# autorewers_Atmega_6.net
KiCad netlist of a schematic drawn in EAGLE
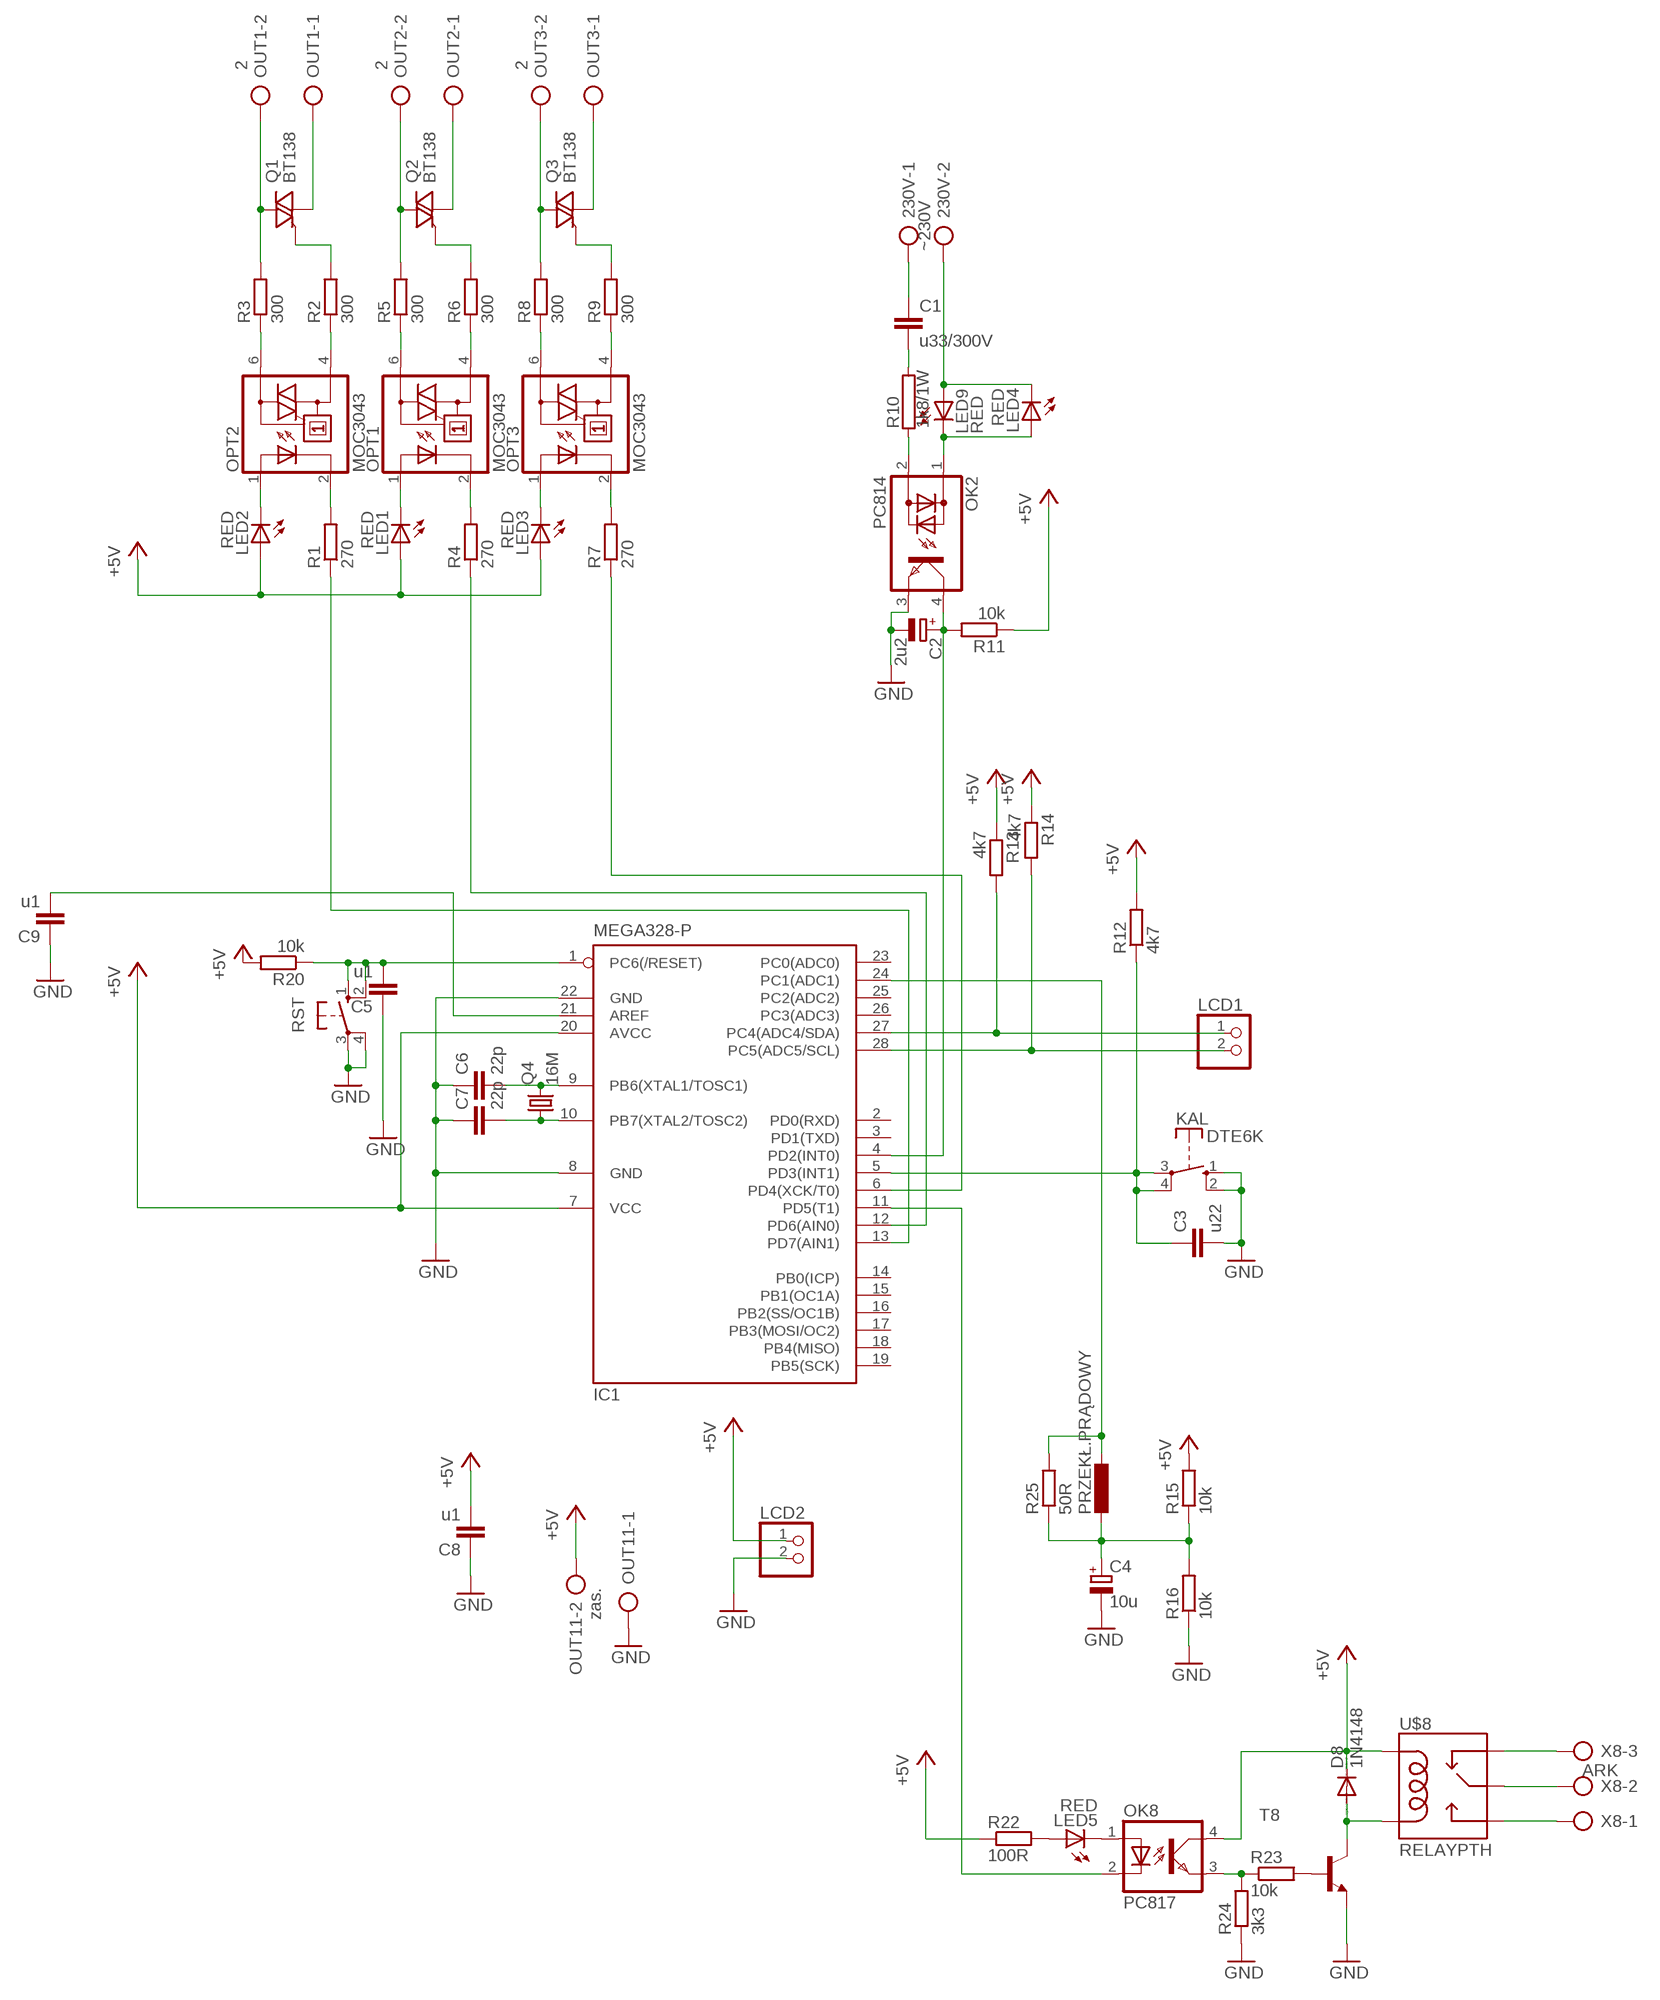
[diagram p0: schematic, sheet 1]

(export (version "E")
  (design (tool "Eeschema 10.0.6"))
  (components
    (comp (ref "230V")
      (value "~230V")
      (footprint "eagle-import:AK500_2")
      (libsource (lib "eagle-import") (part "AK500/2"))
    )
    (comp (ref "C1")
      (value "u33/300V")
      (footprint "eagle-import:C225-087X268")
      (libsource (lib "eagle-import") (part "C-EU225-087X268"))
    )
    (comp (ref "C2")
      (value "2u2")
      (footprint "eagle-import:B45181A")
      (libsource (lib "eagle-import") (part "CPOL-EUB45181A"))
    )
    (comp (ref "C3")
      (value "u22")
      (footprint "eagle-import:C050-025X075")
      (libsource (lib "eagle-import") (part "C-EU050-025X075"))
    )
    (comp (ref "C4")
      (value "10u")
      (footprint "eagle-import:B45181A")
      (libsource (lib "eagle-import") (part "CPOL-EUB45181A"))
    )
    (comp (ref "C5")
      (value "u1")
      (footprint "eagle-import:C050-025X075")
      (libsource (lib "eagle-import") (part "C-EU050-025X075"))
    )
    (comp (ref "C6")
      (value "22p")
      (footprint "eagle-import:C050-025X075")
      (libsource (lib "eagle-import") (part "C-EU050-025X075"))
    )
    (comp (ref "C7")
      (value "22p")
      (footprint "eagle-import:C050-025X075")
      (libsource (lib "eagle-import") (part "C-EU050-025X075"))
    )
    (comp (ref "C8")
      (value "u1")
      (footprint "eagle-import:C050-025X075")
      (libsource (lib "eagle-import") (part "C-EU050-025X075"))
    )
    (comp (ref "C9")
      (value "u1")
      (footprint "eagle-import:C050-025X075")
      (libsource (lib "eagle-import") (part "C-EU050-025X075"))
    )
    (comp (ref "D8")
      (value "1N4148")
      (footprint "eagle-import:DO35-10")
      (libsource (lib "eagle-import") (part "1N4148DO35-10"))
    )
    (comp (ref "IC1")
      (value "MEGA328-P")
      (footprint "eagle-import:DIL28-3")
      (libsource (lib "eagle-import") (part "MEGA8-P"))
    )
    (comp (ref "KAL")
      (value "DTE6K")
      (footprint "eagle-import:DTE6K")
      (libsource (lib "eagle-import") (part "DTE6K"))
    )
    (comp (ref "LCD1")
      (value "PINHD-1X2")
      (footprint "eagle-import:1X02")
      (libsource (lib "eagle-import") (part "PINHD-1X2"))
    )
    (comp (ref "LCD2")
      (value "PINHD-1X2")
      (footprint "eagle-import:1X02")
      (libsource (lib "eagle-import") (part "PINHD-1X2"))
    )
    (comp (ref "LED1")
      (value "RED")
      (footprint "eagle-import:LED3MM")
      (libsource (lib "eagle-import") (part "LED3MM"))
    )
    (comp (ref "LED2")
      (value "RED")
      (footprint "eagle-import:LED3MM")
      (libsource (lib "eagle-import") (part "LED3MM"))
    )
    (comp (ref "LED3")
      (value "RED")
      (footprint "eagle-import:LED3MM")
      (libsource (lib "eagle-import") (part "LED3MM"))
    )
    (comp (ref "LED4")
      (value "RED")
      (footprint "eagle-import:LED3MM")
      (libsource (lib "eagle-import") (part "LED3MM"))
    )
    (comp (ref "LED5")
      (value "RED")
      (footprint "eagle-import:LED3MM")
      (libsource (lib "eagle-import") (part "LED3MM"))
    )
    (comp (ref "LED9")
      (value "RED")
      (footprint "eagle-import:LED3MM")
      (libsource (lib "eagle-import") (part "LED3MM"))
    )
    (comp (ref "OK2")
      (value "PC814")
      (footprint "eagle-import:DIL04")
      (libsource (lib "eagle-import") (part "PC814"))
    )
    (comp (ref "OK8")
      (value "PC817")
      (footprint "eagle-import:DIL04")
      (fields (field (name "MPN") "PC817X4J000F"))
      (libsource (lib "eagle-import") (part "PC817"))
    )
    (comp (ref "OPT1")
      (value "MOC3043")
      (footprint "eagle-import:DIL06")
      (fields
        (field (name "MF") "VISHAY/TELEFUNKEN")
        (field (name "MPN") "IL410")
        (field (name "MF_1") "FAIRCHILD SEMICONDUCTOR")
        (field (name "MPN_1") "MOC3041")
      )
      (libsource (lib "eagle-import") (part "IL410"))
    )
    (comp (ref "OPT2")
      (value "MOC3043")
      (footprint "eagle-import:DIL06")
      (fields
        (field (name "MF") "VISHAY/TELEFUNKEN")
        (field (name "MPN") "IL410")
        (field (name "MF_1") "FAIRCHILD SEMICONDUCTOR")
        (field (name "MPN_1") "MOC3041")
      )
      (libsource (lib "eagle-import") (part "IL410"))
    )
    (comp (ref "OPT3")
      (value "MOC3043")
      (footprint "eagle-import:DIL06")
      (fields
        (field (name "MF") "VISHAY/TELEFUNKEN")
        (field (name "MPN") "IL410")
        (field (name "MF_1") "FAIRCHILD SEMICONDUCTOR")
        (field (name "MPN_1") "MOC3041")
      )
      (libsource (lib "eagle-import") (part "IL410"))
    )
    (comp (ref "OUT1")
      (value "2")
      (footprint "eagle-import:AK500_2")
      (libsource (lib "eagle-import") (part "AK500/2"))
    )
    (comp (ref "OUT2")
      (value "2")
      (footprint "eagle-import:AK500_2")
      (libsource (lib "eagle-import") (part "AK500/2"))
    )
    (comp (ref "OUT3")
      (value "2")
      (footprint "eagle-import:AK500_2")
      (libsource (lib "eagle-import") (part "AK500/2"))
    )
    (comp (ref "OUT11")
      (value "zas.")
      (footprint "eagle-import:AK500_2")
      (libsource (lib "eagle-import") (part "AK500/2"))
    )
    (comp (ref "PRZEKŁ.PRĄDOWY")
      (value "L-EU2200-12.7")
      (footprint "eagle-import:2200-12.7")
      (libsource (lib "eagle-import") (part "L-EU2200-12.7"))
    )
    (comp (ref "Q1")
      (value "BT138")
      (footprint "eagle-import:TO220BV")
      (libsource (lib "eagle-import") (part "BT138-V"))
    )
    (comp (ref "Q2")
      (value "BT138")
      (footprint "eagle-import:TO220BV")
      (libsource (lib "eagle-import") (part "BT138-V"))
    )
    (comp (ref "Q3")
      (value "BT138")
      (footprint "eagle-import:TO220BV")
      (libsource (lib "eagle-import") (part "BT138-V"))
    )
    (comp (ref "Q4")
      (value "16M")
      (footprint "eagle-import:HC49_S")
      (libsource (lib "eagle-import") (part "CRYSTALHC49S"))
    )
    (comp (ref "R1")
      (value "270")
      (footprint "eagle-import:0204_7")
      (libsource (lib "eagle-import") (part "R-EU_0204/7"))
    )
    (comp (ref "R2")
      (value "300")
      (footprint "eagle-import:0204_7")
      (libsource (lib "eagle-import") (part "R-EU_0204/7"))
    )
    (comp (ref "R3")
      (value "300")
      (footprint "eagle-import:0204_7")
      (libsource (lib "eagle-import") (part "R-EU_0204/7"))
    )
    (comp (ref "R4")
      (value "270")
      (footprint "eagle-import:0204_5")
      (libsource (lib "eagle-import") (part "R-EU_0204/5"))
    )
    (comp (ref "R5")
      (value "300")
      (footprint "eagle-import:0204_7")
      (libsource (lib "eagle-import") (part "R-EU_0204/7"))
    )
    (comp (ref "R6")
      (value "300")
      (footprint "eagle-import:0204_7")
      (libsource (lib "eagle-import") (part "R-EU_0204/7"))
    )
    (comp (ref "R7")
      (value "270")
      (footprint "eagle-import:0617_22")
      (libsource (lib "eagle-import") (part "R-EU_0617/22"))
    )
    (comp (ref "R8")
      (value "300")
      (footprint "eagle-import:0204_7")
      (libsource (lib "eagle-import") (part "R-EU_0204/7"))
    )
    (comp (ref "R9")
      (value "300")
      (footprint "eagle-import:0204_7")
      (libsource (lib "eagle-import") (part "R-EU_0204/7"))
    )
    (comp (ref "R10")
      (value "1k8/1W")
      (footprint "eagle-import:AC01")
      (libsource (lib "eagle-import") (part "RAC01"))
    )
    (comp (ref "R11")
      (value "10k")
      (footprint "eagle-import:0207_10")
      (libsource (lib "eagle-import") (part "R-EU_0207/10"))
    )
    (comp (ref "R12")
      (value "4k7")
      (footprint "eagle-import:0204_7")
      (libsource (lib "eagle-import") (part "R-EU_0204/7"))
    )
    (comp (ref "R13")
      (value "4k7")
      (footprint "eagle-import:0204_7")
      (libsource (lib "eagle-import") (part "R-EU_0204/7"))
    )
    (comp (ref "R14")
      (value "4k7")
      (footprint "eagle-import:0204_7")
      (libsource (lib "eagle-import") (part "R-EU_0204/7"))
    )
    (comp (ref "R15")
      (value "10k")
      (footprint "eagle-import:0204_7")
      (libsource (lib "eagle-import") (part "R-EU_0204/7"))
    )
    (comp (ref "R16")
      (value "10k")
      (footprint "eagle-import:0204_7")
      (libsource (lib "eagle-import") (part "R-EU_0204/7"))
    )
    (comp (ref "R20")
      (value "10k")
      (footprint "eagle-import:0207_15")
      (libsource (lib "eagle-import") (part "R-EU_0207/15"))
    )
    (comp (ref "R22")
      (value "100R")
      (footprint "eagle-import:0207_10")
      (libsource (lib "eagle-import") (part "resistor_R-EU_0207/10"))
    )
    (comp (ref "R23")
      (value "10k")
      (footprint "eagle-import:0204_5")
      (libsource (lib "eagle-import") (part "resistor_R-EU_0204/5"))
    )
    (comp (ref "R24")
      (value "3k3")
      (footprint "eagle-import:0204_7")
      (libsource (lib "eagle-import") (part "resistor_R-EU_0204/7"))
    )
    (comp (ref "R25")
      (value "50R")
      (footprint "eagle-import:0204_7")
      (libsource (lib "eagle-import") (part "R-EU_0204/7"))
    )
    (comp (ref "RST")
      (value "10-XX")
      (footprint "eagle-import:B3F-10XX")
      (fields (field (name "MPN") "B3F-1000"))
      (libsource (lib "eagle-import") (part "10-XX"))
    )
    (comp (ref "T8")
      (value "BC237-NPN-TO92-CBE")
      (footprint "eagle-import:TO92-CBE")
      (libsource (lib "eagle-import") (part "-NPN-TO92-CBEBC237"))
    )
    (comp (ref "U$8")
      (value "RELAYPTH")
      (footprint "eagle-import:SRD-05VDC-SL-C")
      (libsource (lib "eagle-import") (part "RELAYPTH"))
    )
    (comp (ref "X8")
      (value "ARK")
      (footprint "eagle-import:AK300_3")
      (libsource (lib "eagle-import") (part "AK300/3"))
    )
  )
  (nets
    (net (code "1") (name "+5V") (class "Default")
      (node (ref "C8") (pin "2") (pinfunction "2_2") (pintype "passive"))
      (node (ref "D8") (pin "C") (pinfunction "C_C") (pintype "passive"))
      (node (ref "IC1") (pin "20") (pinfunction "AVCC_20") (pintype "power_in"))
      (node (ref "IC1") (pin "7") (pinfunction "VCC_7") (pintype "power_in"))
      (node (ref "LCD2") (pin "1") (pinfunction "1_1") (pintype "passive"))
      (node (ref "LED1") (pin "A") (pinfunction "A_A") (pintype "passive"))
      (node (ref "LED2") (pin "A") (pinfunction "A_A") (pintype "passive"))
      (node (ref "LED3") (pin "A") (pinfunction "A_A") (pintype "passive"))
      (node (ref "OK8") (pin "4") (pinfunction "COL_4") (pintype "passive"))
      (node (ref "OUT11") (pin "2") (pinfunction "KL_2") (pintype "passive"))
      (node (ref "R11") (pin "1") (pinfunction "1_1") (pintype "passive"))
      (node (ref "R12") (pin "2") (pinfunction "2_2") (pintype "passive"))
      (node (ref "R13") (pin "1") (pinfunction "1_1") (pintype "passive"))
      (node (ref "R14") (pin "1") (pinfunction "1_1") (pintype "passive"))
      (node (ref "R15") (pin "2") (pinfunction "2_2") (pintype "passive"))
      (node (ref "R20") (pin "2") (pinfunction "2_2") (pintype "passive"))
      (node (ref "R22") (pin "1") (pinfunction "1_1") (pintype "passive"))
      (node (ref "U$8") (pin "COIL1") (pinfunction "COIL1_COIL1") (pintype "bidirectional"))
    )
    (net (code "2") (name "GND") (class "Default")
      (node (ref "C2") (pin "-") (pinfunction "-_-") (pintype "passive"))
      (node (ref "C3") (pin "2") (pinfunction "2_2") (pintype "passive"))
      (node (ref "C4") (pin "-") (pinfunction "-_-") (pintype "passive"))
      (node (ref "C5") (pin "1") (pinfunction "1_1") (pintype "passive"))
      (node (ref "C6") (pin "1") (pinfunction "1_1") (pintype "passive"))
      (node (ref "C7") (pin "1") (pinfunction "1_1") (pintype "passive"))
      (node (ref "C8") (pin "1") (pinfunction "1_1") (pintype "passive"))
      (node (ref "C9") (pin "1") (pinfunction "1_1") (pintype "passive"))
      (node (ref "IC1") (pin "22") (pinfunction "GND_22") (pintype "power_in"))
      (node (ref "IC1") (pin "8") (pinfunction "GND_8") (pintype "power_in"))
      (node (ref "KAL") (pin "1") (pinfunction "S_1") (pintype "passive"))
      (node (ref "KAL") (pin "2") (pinfunction "S_2") (pintype "passive"))
      (node (ref "LCD2") (pin "2") (pinfunction "2_2") (pintype "passive"))
      (node (ref "OK2") (pin "3") (pinfunction "E_3") (pintype "passive"))
      (node (ref "OUT11") (pin "1") (pinfunction "KL_1") (pintype "passive"))
      (node (ref "R16") (pin "1") (pinfunction "1_1") (pintype "passive"))
      (node (ref "R24") (pin "1") (pinfunction "1_1") (pintype "passive"))
      (node (ref "RST") (pin "3") (pinfunction "P_3") (pintype "passive"))
      (node (ref "RST") (pin "4") (pinfunction "P1_4") (pintype "passive"))
      (node (ref "T8") (pin "E") (pinfunction "E_E") (pintype "passive"))
    )
    (net (code "3") (name "Net-(230VA-KL)") (class "Default")
      (node (ref "230V") (pin "1") (pinfunction "KL_1") (pintype "passive"))
      (node (ref "C1") (pin "1") (pinfunction "1_1") (pintype "passive"))
    )
    (net (code "4") (name "Net-(230VB-KL)") (class "Default")
      (node (ref "230V") (pin "2") (pinfunction "KL_2") (pintype "passive"))
      (node (ref "LED4") (pin "K") (pinfunction "C_K") (pintype "passive"))
      (node (ref "LED9") (pin "A") (pinfunction "A_A") (pintype "passive"))
    )
    (net (code "5") (name "Net-(C1-Pad2)") (class "Default")
      (node (ref "C1") (pin "2") (pinfunction "2_2") (pintype "passive"))
      (node (ref "R10") (pin "2") (pinfunction "2_2") (pintype "passive"))
    )
    (net (code "6") (name "Net-(C4-Pad+)") (class "Default")
      (node (ref "C4") (pin "+") (pinfunction "+_+") (pintype "passive"))
      (node (ref "PRZEKŁ.PRĄDOWY") (pin "2") (pinfunction "2_2") (pintype "passive"))
      (node (ref "R15") (pin "1") (pinfunction "1_1") (pintype "passive"))
      (node (ref "R16") (pin "2") (pinfunction "2_2") (pintype "passive"))
      (node (ref "R25") (pin "1") (pinfunction "1_1") (pintype "passive"))
    )
    (net (code "7") (name "Net-(D8-PadA)") (class "Default")
      (node (ref "D8") (pin "A") (pinfunction "A_A") (pintype "passive"))
      (node (ref "T8") (pin "C") (pinfunction "C_C") (pintype "passive"))
      (node (ref "U$8") (pin "COIL0") (pinfunction "COIL0_COIL0") (pintype "bidirectional"))
    )
    (net (code "8") (name "Net-(IC1-AREF)") (class "Default")
      (node (ref "C9") (pin "2") (pinfunction "2_2") (pintype "passive"))
      (node (ref "IC1") (pin "21") (pinfunction "AREF_21") (pintype "passive"))
    )
    (net (code "9") (name "Net-(IC1-PB6(XTAL1{slash}TOSC1))") (class "Default")
      (node (ref "C6") (pin "2") (pinfunction "2_2") (pintype "passive"))
      (node (ref "IC1") (pin "9") (pinfunction "PB6(XTAL1/TOSC1)_9") (pintype "bidirectional"))
      (node (ref "Q4") (pin "2") (pinfunction "2_2") (pintype "passive"))
    )
    (net (code "10") (name "Net-(IC1-PB7(XTAL2{slash}TOSC2))") (class "Default")
      (node (ref "C7") (pin "2") (pinfunction "2_2") (pintype "passive"))
      (node (ref "IC1") (pin "10") (pinfunction "PB7(XTAL2/TOSC2)_10") (pintype "bidirectional"))
      (node (ref "Q4") (pin "1") (pinfunction "1_1") (pintype "passive"))
    )
    (net (code "11") (name "Net-(IC1-PC1(ADC1))") (class "Default")
      (node (ref "IC1") (pin "24") (pinfunction "PC1(ADC1)_24") (pintype "bidirectional"))
      (node (ref "PRZEKŁ.PRĄDOWY") (pin "1") (pinfunction "1_1") (pintype "passive"))
      (node (ref "R25") (pin "2") (pinfunction "2_2") (pintype "passive"))
    )
    (net (code "12") (name "Net-(IC1-PC4(ADC4{slash}SDA))") (class "Default")
      (node (ref "IC1") (pin "27") (pinfunction "PC4(ADC4/SDA)_27") (pintype "bidirectional"))
      (node (ref "LCD1") (pin "1") (pinfunction "1_1") (pintype "passive"))
      (node (ref "R13") (pin "2") (pinfunction "2_2") (pintype "passive"))
    )
    (net (code "13") (name "Net-(IC1-PC5(ADC5{slash}SCL))") (class "Default")
      (node (ref "IC1") (pin "28") (pinfunction "PC5(ADC5/SCL)_28") (pintype "bidirectional"))
      (node (ref "LCD1") (pin "2") (pinfunction "2_2") (pintype "passive"))
      (node (ref "R14") (pin "2") (pinfunction "2_2") (pintype "passive"))
    )
    (net (code "14") (name "Net-(IC1-PC6({slash}RESET))") (class "Default")
      (node (ref "C5") (pin "2") (pinfunction "2_2") (pintype "passive"))
      (node (ref "IC1") (pin "1") (pinfunction "PC6(/RESET)_1") (pintype "bidirectional"))
      (node (ref "R20") (pin "1") (pinfunction "1_1") (pintype "passive"))
      (node (ref "RST") (pin "1") (pinfunction "S_1") (pintype "passive"))
      (node (ref "RST") (pin "2") (pinfunction "S1_2") (pintype "passive"))
    )
    (net (code "15") (name "Net-(IC1-PD2(INT0))") (class "Default")
      (node (ref "C2") (pin "+") (pinfunction "+_+") (pintype "passive"))
      (node (ref "IC1") (pin "4") (pinfunction "PD2(INT0)_4") (pintype "bidirectional"))
      (node (ref "OK2") (pin "4") (pinfunction "C_4") (pintype "passive"))
      (node (ref "R11") (pin "2") (pinfunction "2_2") (pintype "passive"))
    )
    (net (code "16") (name "Net-(IC1-PD3(INT1))") (class "Default")
      (node (ref "C3") (pin "1") (pinfunction "1_1") (pintype "passive"))
      (node (ref "IC1") (pin "5") (pinfunction "PD3(INT1)_5") (pintype "bidirectional"))
      (node (ref "KAL") (pin "3") (pinfunction "P_3") (pintype "passive"))
      (node (ref "KAL") (pin "4") (pinfunction "P_4") (pintype "passive"))
      (node (ref "R12") (pin "1") (pinfunction "1_1") (pintype "passive"))
    )
    (net (code "17") (name "Net-(IC1-PD4(XCK{slash}T0))") (class "Default")
      (node (ref "IC1") (pin "6") (pinfunction "PD4(XCK/T0)_6") (pintype "bidirectional"))
      (node (ref "R7") (pin "1") (pinfunction "1_1") (pintype "passive"))
    )
    (net (code "18") (name "Net-(IC1-PD5(T1))") (class "Default")
      (node (ref "IC1") (pin "11") (pinfunction "PD5(T1)_11") (pintype "bidirectional"))
      (node (ref "OK8") (pin "2") (pinfunction "C_2") (pintype "passive"))
    )
    (net (code "19") (name "Net-(IC1-PD6(AIN0))") (class "Default")
      (node (ref "IC1") (pin "12") (pinfunction "PD6(AIN0)_12") (pintype "bidirectional"))
      (node (ref "R4") (pin "1") (pinfunction "1_1") (pintype "passive"))
    )
    (net (code "20") (name "Net-(IC1-PD7(AIN1))") (class "Default")
      (node (ref "IC1") (pin "13") (pinfunction "PD7(AIN1)_13") (pintype "bidirectional"))
      (node (ref "R1") (pin "1") (pinfunction "1_1") (pintype "passive"))
    )
    (net (code "21") (name "Net-(LED1-C)") (class "Default")
      (node (ref "LED1") (pin "K") (pinfunction "C_K") (pintype "passive"))
      (node (ref "OPT1") (pin "1") (pinfunction "A_1") (pintype "passive"))
    )
    (net (code "22") (name "Net-(LED2-C)") (class "Default")
      (node (ref "LED2") (pin "K") (pinfunction "C_K") (pintype "passive"))
      (node (ref "OPT2") (pin "1") (pinfunction "A_1") (pintype "passive"))
    )
    (net (code "23") (name "Net-(LED3-C)") (class "Default")
      (node (ref "LED3") (pin "K") (pinfunction "C_K") (pintype "passive"))
      (node (ref "OPT3") (pin "1") (pinfunction "A_1") (pintype "passive"))
    )
    (net (code "24") (name "Net-(LED5-C)") (class "Default")
      (node (ref "LED5") (pin "K") (pinfunction "C_K") (pintype "passive"))
      (node (ref "OK8") (pin "1") (pinfunction "A_1") (pintype "passive"))
    )
    (net (code "25") (name "Net-(LED5-PadA)") (class "Default")
      (node (ref "LED5") (pin "A") (pinfunction "A_A") (pintype "passive"))
      (node (ref "R22") (pin "2") (pinfunction "2_2") (pintype "passive"))
    )
    (net (code "26") (name "Net-(LED9-C)") (class "Default")
      (node (ref "LED4") (pin "A") (pinfunction "A_A") (pintype "passive"))
      (node (ref "LED9") (pin "K") (pinfunction "C_K") (pintype "passive"))
      (node (ref "OK2") (pin "1") (pinfunction "AC1_1") (pintype "passive"))
    )
    (net (code "27") (name "Net-(OK2-AC2)") (class "Default")
      (node (ref "OK2") (pin "2") (pinfunction "AC2_2") (pintype "passive"))
      (node (ref "R10") (pin "1") (pinfunction "1_1") (pintype "passive"))
    )
    (net (code "28") (name "Net-(OK8-EMIT)") (class "Default")
      (node (ref "OK8") (pin "3") (pinfunction "EMIT_3") (pintype "passive"))
      (node (ref "R23") (pin "1") (pinfunction "1_1") (pintype "passive"))
      (node (ref "R24") (pin "2") (pinfunction "2_2") (pintype "passive"))
    )
    (net (code "29") (name "Net-(OPT1-A1)") (class "Default")
      (node (ref "OPT1") (pin "4") (pinfunction "A1_4") (pintype "passive"))
      (node (ref "R6") (pin "1") (pinfunction "1_1") (pintype "passive"))
    )
    (net (code "30") (name "Net-(OPT1-A2)") (class "Default")
      (node (ref "OPT1") (pin "6") (pinfunction "A2_6") (pintype "passive"))
      (node (ref "R5") (pin "1") (pinfunction "1_1") (pintype "passive"))
    )
    (net (code "31") (name "Net-(OPT1-C)") (class "Default")
      (node (ref "OPT1") (pin "2") (pinfunction "C_2") (pintype "passive"))
      (node (ref "R4") (pin "2") (pinfunction "2_2") (pintype "passive"))
    )
    (net (code "32") (name "Net-(OPT2-A1)") (class "Default")
      (node (ref "OPT2") (pin "4") (pinfunction "A1_4") (pintype "passive"))
      (node (ref "R2") (pin "1") (pinfunction "1_1") (pintype "passive"))
    )
    (net (code "33") (name "Net-(OPT2-A2)") (class "Default")
      (node (ref "OPT2") (pin "6") (pinfunction "A2_6") (pintype "passive"))
      (node (ref "R3") (pin "1") (pinfunction "1_1") (pintype "passive"))
    )
    (net (code "34") (name "Net-(OPT2-C)") (class "Default")
      (node (ref "OPT2") (pin "2") (pinfunction "C_2") (pintype "passive"))
      (node (ref "R1") (pin "2") (pinfunction "2_2") (pintype "passive"))
    )
    (net (code "35") (name "Net-(OPT3-A1)") (class "Default")
      (node (ref "OPT3") (pin "4") (pinfunction "A1_4") (pintype "passive"))
      (node (ref "R9") (pin "1") (pinfunction "1_1") (pintype "passive"))
    )
    (net (code "36") (name "Net-(OPT3-A2)") (class "Default")
      (node (ref "OPT3") (pin "6") (pinfunction "A2_6") (pintype "passive"))
      (node (ref "R8") (pin "1") (pinfunction "1_1") (pintype "passive"))
    )
    (net (code "37") (name "Net-(OPT3-C)") (class "Default")
      (node (ref "OPT3") (pin "2") (pinfunction "C_2") (pintype "passive"))
      (node (ref "R7") (pin "2") (pinfunction "2_2") (pintype "passive"))
    )
    (net (code "38") (name "Net-(OUT1A-KL)") (class "Default")
      (node (ref "OUT1") (pin "1") (pinfunction "KL_1") (pintype "passive"))
      (node (ref "Q1") (pin "T1") (pinfunction "A1_T1") (pintype "passive"))
    )
    (net (code "39") (name "Net-(OUT1B-KL)") (class "Default")
      (node (ref "OUT1") (pin "2") (pinfunction "KL_2") (pintype "passive"))
      (node (ref "Q1") (pin "T2") (pinfunction "A2_T2") (pintype "passive"))
      (node (ref "R3") (pin "2") (pinfunction "2_2") (pintype "passive"))
    )
    (net (code "40") (name "Net-(OUT2A-KL)") (class "Default")
      (node (ref "OUT2") (pin "1") (pinfunction "KL_1") (pintype "passive"))
      (node (ref "Q2") (pin "T1") (pinfunction "A1_T1") (pintype "passive"))
    )
    (net (code "41") (name "Net-(OUT2B-KL)") (class "Default")
      (node (ref "OUT2") (pin "2") (pinfunction "KL_2") (pintype "passive"))
      (node (ref "Q2") (pin "T2") (pinfunction "A2_T2") (pintype "passive"))
      (node (ref "R5") (pin "2") (pinfunction "2_2") (pintype "passive"))
    )
    (net (code "42") (name "Net-(OUT3A-KL)") (class "Default")
      (node (ref "OUT3") (pin "1") (pinfunction "KL_1") (pintype "passive"))
      (node (ref "Q3") (pin "T1") (pinfunction "A1_T1") (pintype "passive"))
    )
    (net (code "43") (name "Net-(OUT3B-KL)") (class "Default")
      (node (ref "OUT3") (pin "2") (pinfunction "KL_2") (pintype "passive"))
      (node (ref "Q3") (pin "T2") (pinfunction "A2_T2") (pintype "passive"))
      (node (ref "R8") (pin "2") (pinfunction "2_2") (pintype "passive"))
    )
    (net (code "44") (name "Net-(Q1-PadG)") (class "Default")
      (node (ref "Q1") (pin "G") (pinfunction "G_G") (pintype "passive"))
      (node (ref "R2") (pin "2") (pinfunction "2_2") (pintype "passive"))
    )
    (net (code "45") (name "Net-(Q2-PadG)") (class "Default")
      (node (ref "Q2") (pin "G") (pinfunction "G_G") (pintype "passive"))
      (node (ref "R6") (pin "2") (pinfunction "2_2") (pintype "passive"))
    )
    (net (code "46") (name "Net-(Q3-PadG)") (class "Default")
      (node (ref "Q3") (pin "G") (pinfunction "G_G") (pintype "passive"))
      (node (ref "R9") (pin "2") (pinfunction "2_2") (pintype "passive"))
    )
    (net (code "47") (name "Net-(R23-Pad2)") (class "Default")
      (node (ref "R23") (pin "2") (pinfunction "2_2") (pintype "passive"))
      (node (ref "T8") (pin "B") (pinfunction "B_B") (pintype "passive"))
    )
    (net (code "48") (name "Net-(U$8-SWCLOSE)") (class "Default")
      (node (ref "U$8") (pin "SWCLOSED") (pinfunction "SWCLOSE_SWCLOSED") (pintype "bidirectional"))
      (node (ref "X8") (pin "3") (pinfunction "KL_3") (pintype "passive"))
    )
    (net (code "49") (name "Net-(X8A-KL)") (class "Default")
      (node (ref "U$8") (pin "SWOPEN") (pinfunction "SWOPEN_SWOPEN") (pintype "bidirectional"))
      (node (ref "X8") (pin "1") (pinfunction "KL_1") (pintype "passive"))
    )
    (net (code "50") (name "Net-(X8B-KL)") (class "Default")
      (node (ref "U$8") (pin "SWCOMMON") (pinfunction "SWCOMMON_SWCOMMON") (pintype "bidirectional"))
      (node (ref "X8") (pin "2") (pinfunction "KL_2") (pintype "passive"))
    )
    (net (code "51") (name "unconnected-(IC1-PB0(ICP)-Pad14)") (class "Default")
      (node (ref "IC1") (pin "14") (pinfunction "PB0(ICP)_14") (pintype "bidirectional"))
    )
    (net (code "52") (name "unconnected-(IC1-PB1(OC1A)-Pad15)") (class "Default")
      (node (ref "IC1") (pin "15") (pinfunction "PB1(OC1A)_15") (pintype "bidirectional"))
    )
    (net (code "53") (name "unconnected-(IC1-PB2(SS{slash}OC1B)-Pad16)") (class "Default")
      (node (ref "IC1") (pin "16") (pinfunction "PB2(SS/OC1B)_16") (pintype "bidirectional"))
    )
    (net (code "54") (name "unconnected-(IC1-PB3(MOSI{slash}OC2)-Pad17)") (class "Default")
      (node (ref "IC1") (pin "17") (pinfunction "PB3(MOSI/OC2)_17") (pintype "bidirectional"))
    )
    (net (code "55") (name "unconnected-(IC1-PB4(MISO)-Pad18)") (class "Default")
      (node (ref "IC1") (pin "18") (pinfunction "PB4(MISO)_18") (pintype "bidirectional"))
    )
    (net (code "56") (name "unconnected-(IC1-PB5(SCK)-Pad19)") (class "Default")
      (node (ref "IC1") (pin "19") (pinfunction "PB5(SCK)_19") (pintype "bidirectional"))
    )
    (net (code "57") (name "unconnected-(IC1-PC0(ADC0)-Pad23)") (class "Default")
      (node (ref "IC1") (pin "23") (pinfunction "PC0(ADC0)_23") (pintype "bidirectional"))
    )
    (net (code "58") (name "unconnected-(IC1-PC2(ADC2)-Pad25)") (class "Default")
      (node (ref "IC1") (pin "25") (pinfunction "PC2(ADC2)_25") (pintype "bidirectional"))
    )
    (net (code "59") (name "unconnected-(IC1-PC3(ADC3)-Pad26)") (class "Default")
      (node (ref "IC1") (pin "26") (pinfunction "PC3(ADC3)_26") (pintype "bidirectional"))
    )
    (net (code "60") (name "unconnected-(IC1-PD0(RXD)-Pad2)") (class "Default")
      (node (ref "IC1") (pin "2") (pinfunction "PD0(RXD)_2") (pintype "bidirectional"))
    )
    (net (code "61") (name "unconnected-(IC1-PD1(TXD)-Pad3)") (class "Default")
      (node (ref "IC1") (pin "3") (pinfunction "PD1(TXD)_3") (pintype "bidirectional"))
    )
  )
)
